# Control.net
KiCad netlist of a schematic drawn in Altium Designer
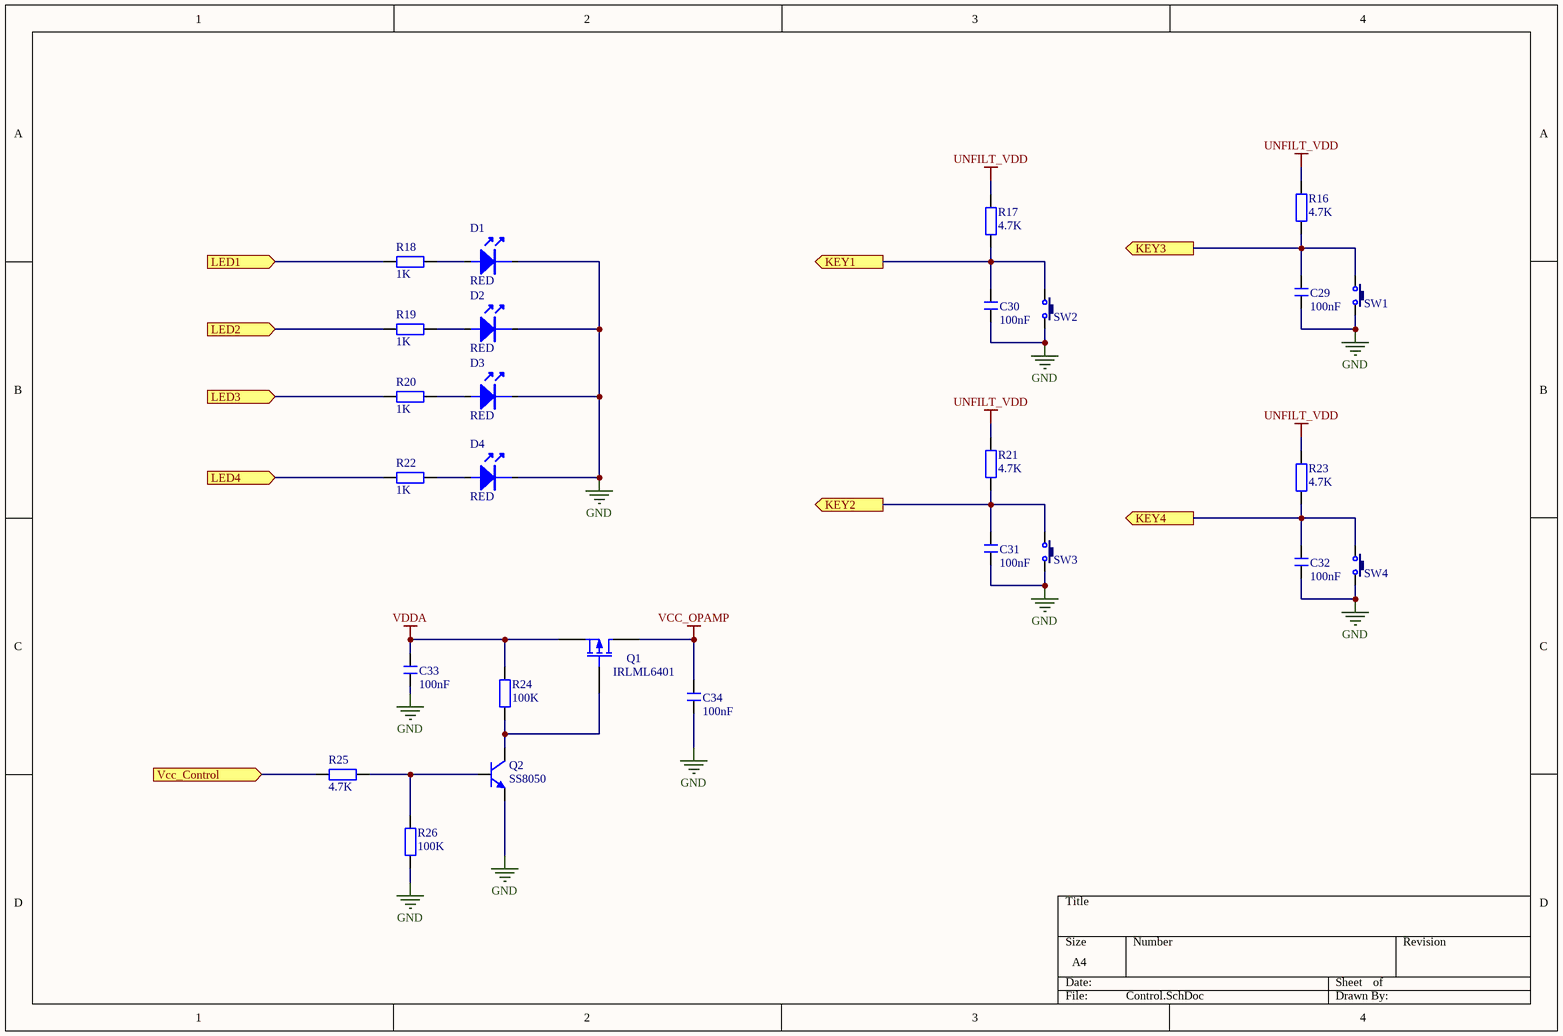
[diagram p0: Control.SchDoc]

(export (version "E")
  (design (tool "Eeschema 10.0.6"))
  (components
    (comp (ref "C29")
      (value "100nF")
      (footprint "C 0603_L")
      (description "贴片电容")
      (libsource (lib "0.1 - 电阻-电容-电感") (part "C"))
    )
    (comp (ref "C30")
      (value "100nF")
      (footprint "C 0603_L")
      (description "贴片电容")
      (libsource (lib "0.1 - 电阻-电容-电感") (part "C"))
    )
    (comp (ref "C31")
      (value "100nF")
      (footprint "C 0603_L")
      (description "贴片电容")
      (libsource (lib "0.1 - 电阻-电容-电感") (part "C"))
    )
    (comp (ref "C32")
      (value "100nF")
      (footprint "C 0603_L")
      (description "贴片电容")
      (libsource (lib "0.1 - 电阻-电容-电感") (part "C"))
    )
    (comp (ref "C33")
      (value "100nF")
      (footprint "C 0603_L")
      (description "贴片电容")
      (libsource (lib "0.1 - 电阻-电容-电感") (part "C"))
    )
    (comp (ref "C34")
      (value "100nF")
      (footprint "C 0603_L")
      (description "贴片电容")
      (libsource (lib "0.1 - 电阻-电容-电感") (part "C"))
    )
    (comp (ref "D1") (value "RED") (footprint "0603D") (libsource (lib "YS-F1Pro开发板主板") (part "LED")))
    (comp (ref "D2") (value "RED") (footprint "0603D") (libsource (lib "YS-F1Pro开发板主板") (part "LED")))
    (comp (ref "D3") (value "RED") (footprint "0603D") (libsource (lib "YS-F1Pro开发板主板") (part "LED")))
    (comp (ref "D4") (value "RED") (footprint "0603D") (libsource (lib "YS-F1Pro开发板主板") (part "LED")))
    (comp (ref "Q1")
      (value "IRLML6401")
      (footprint "mini_rlc:SOT-23_N")
      (description "P-Channel MOSFET")
      (fields (field (name "PUBLISHER") "Altium Limited"))
      (libsource (lib "Miscellaneous Devices") (part "MOSFET-P"))
    )
    (comp (ref "Q2")
      (value "SS8050")
      (footprint "SOT23-3N")
      (description "高频放大-NPN型")
      (fields (field (name "版权归属") "封装库来自淘宝 ID：黄晶宝石"))
      (libsource (lib "0.4 - 三极管") (part "8050-SMD"))
    )
    (comp (ref "R16")
      (value "4.7K")
      (footprint "R 0603_L")
      (description "贴片电阻")
      (fields (field (name "版权归属") "来自淘宝 ID：黄晶宝石"))
      (libsource (lib "0.1 - 电阻-电容-电感") (part "R"))
    )
    (comp (ref "R17")
      (value "4.7K")
      (footprint "R 0603_L")
      (description "贴片电阻")
      (fields (field (name "版权归属") "来自淘宝 ID：黄晶宝石"))
      (libsource (lib "0.1 - 电阻-电容-电感") (part "R"))
    )
    (comp (ref "R18")
      (value "1K")
      (footprint "R 0603_L")
      (description "贴片电阻")
      (fields (field (name "版权归属") "来自淘宝 ID：黄晶宝石"))
      (libsource (lib "0.1 - 电阻-电容-电感") (part "R"))
    )
    (comp (ref "R19")
      (value "1K")
      (footprint "R 0603_L")
      (description "贴片电阻")
      (fields (field (name "版权归属") "来自淘宝 ID：黄晶宝石"))
      (libsource (lib "0.1 - 电阻-电容-电感") (part "R"))
    )
    (comp (ref "R20")
      (value "1K")
      (footprint "R 0603_L")
      (description "贴片电阻")
      (fields (field (name "版权归属") "来自淘宝 ID：黄晶宝石"))
      (libsource (lib "0.1 - 电阻-电容-电感") (part "R"))
    )
    (comp (ref "R21")
      (value "4.7K")
      (footprint "R 0603_L")
      (description "贴片电阻")
      (fields (field (name "版权归属") "来自淘宝 ID：黄晶宝石"))
      (libsource (lib "0.1 - 电阻-电容-电感") (part "R"))
    )
    (comp (ref "R22")
      (value "1K")
      (footprint "R 0603_L")
      (description "贴片电阻")
      (fields (field (name "版权归属") "来自淘宝 ID：黄晶宝石"))
      (libsource (lib "0.1 - 电阻-电容-电感") (part "R"))
    )
    (comp (ref "R23")
      (value "4.7K")
      (footprint "R 0603_L")
      (description "贴片电阻")
      (fields (field (name "版权归属") "来自淘宝 ID：黄晶宝石"))
      (libsource (lib "0.1 - 电阻-电容-电感") (part "R"))
    )
    (comp (ref "R24")
      (value "100K")
      (footprint "R 0603_L")
      (description "贴片电阻")
      (fields (field (name "版权归属") "来自淘宝 ID：黄晶宝石"))
      (libsource (lib "0.1 - 电阻-电容-电感") (part "R"))
    )
    (comp (ref "R25")
      (value "4.7K")
      (footprint "R 0603_L")
      (description "贴片电阻")
      (fields (field (name "版权归属") "来自淘宝 ID：黄晶宝石"))
      (libsource (lib "0.1 - 电阻-电容-电感") (part "R"))
    )
    (comp (ref "R26")
      (value "100K")
      (footprint "R 0603_L")
      (description "贴片电阻")
      (fields (field (name "版权归属") "来自淘宝 ID：黄晶宝石"))
      (libsource (lib "0.1 - 电阻-电容-电感") (part "R"))
    )
    (comp (ref "SW1")
      (value "3x6x5")
      (footprint "TSW SMD-3*6*2.5")
      (description "3x6轻触开关")
      (fields (field (name "版权归属") "封装库来自淘宝 ID：黄晶宝石"))
      (libsource (lib "0.7 - 常用按键-开关") (part "TSW 3x6"))
    )
    (comp (ref "SW2")
      (value "3x6x5")
      (footprint "TSW SMD-3*6*2.5")
      (description "3x6轻触开关")
      (fields (field (name "版权归属") "封装库来自淘宝 ID：黄晶宝石"))
      (libsource (lib "0.7 - 常用按键-开关") (part "TSW 3x6"))
    )
    (comp (ref "SW3")
      (value "3x6x5")
      (footprint "TSW SMD-3*6*2.5")
      (description "3x6轻触开关")
      (fields (field (name "版权归属") "封装库来自淘宝 ID：黄晶宝石"))
      (libsource (lib "0.7 - 常用按键-开关") (part "TSW 3x6"))
    )
    (comp (ref "SW4")
      (value "3x6x5")
      (footprint "TSW SMD-3*6*2.5")
      (description "3x6轻触开关")
      (fields (field (name "版权归属") "封装库来自淘宝 ID：黄晶宝石"))
      (libsource (lib "0.7 - 常用按键-开关") (part "TSW 3x6"))
    )
  )
  (nets
    (net (code "1") (name "/KEY1") (class "Default")
      (node (ref "C30") (pin "1") (pinfunction "1_1") (pintype "passive"))
      (node (ref "R17") (pin "1") (pinfunction "1_1") (pintype "passive"))
      (node (ref "SW2") (pin "1") (pinfunction "1_1") (pintype "passive"))
    )
    (net (code "2") (name "/KEY2") (class "Default")
      (node (ref "C31") (pin "1") (pinfunction "1_1") (pintype "passive"))
      (node (ref "R21") (pin "1") (pinfunction "1_1") (pintype "passive"))
      (node (ref "SW3") (pin "1") (pinfunction "1_1") (pintype "passive"))
    )
    (net (code "3") (name "/KEY3") (class "Default")
      (node (ref "C29") (pin "1") (pinfunction "1_1") (pintype "passive"))
      (node (ref "R16") (pin "1") (pinfunction "1_1") (pintype "passive"))
      (node (ref "SW1") (pin "1") (pinfunction "1_1") (pintype "passive"))
    )
    (net (code "4") (name "/KEY4") (class "Default")
      (node (ref "C32") (pin "1") (pinfunction "1_1") (pintype "passive"))
      (node (ref "R23") (pin "1") (pinfunction "1_1") (pintype "passive"))
      (node (ref "SW4") (pin "1") (pinfunction "1_1") (pintype "passive"))
    )
    (net (code "5") (name "/LED1") (class "Default")
      (node (ref "R18") (pin "1") (pinfunction "1_1") (pintype "passive"))
    )
    (net (code "6") (name "/LED2") (class "Default")
      (node (ref "R19") (pin "1") (pinfunction "1_1") (pintype "passive"))
    )
    (net (code "7") (name "/LED3") (class "Default")
      (node (ref "R20") (pin "1") (pinfunction "1_1") (pintype "passive"))
    )
    (net (code "8") (name "/LED4") (class "Default")
      (node (ref "R22") (pin "1") (pinfunction "1_1") (pintype "passive"))
    )
    (net (code "9") (name "/Vcc_Control") (class "Default")
      (node (ref "R25") (pin "2") (pinfunction "2_2") (pintype "passive"))
    )
    (net (code "10") (name "GND") (class "Default")
      (node (ref "C29") (pin "2") (pinfunction "2_2") (pintype "passive"))
      (node (ref "C30") (pin "2") (pinfunction "2_2") (pintype "passive"))
      (node (ref "C31") (pin "2") (pinfunction "2_2") (pintype "passive"))
      (node (ref "C32") (pin "2") (pinfunction "2_2") (pintype "passive"))
      (node (ref "C33") (pin "1") (pinfunction "1_1") (pintype "passive"))
      (node (ref "C34") (pin "1") (pinfunction "1_1") (pintype "passive"))
      (node (ref "D1") (pin "2") (pinfunction "2_2") (pintype "passive"))
      (node (ref "D2") (pin "2") (pinfunction "2_2") (pintype "passive"))
      (node (ref "D3") (pin "2") (pinfunction "2_2") (pintype "passive"))
      (node (ref "D4") (pin "2") (pinfunction "2_2") (pintype "passive"))
      (node (ref "Q2") (pin "2") (pinfunction "E_2") (pintype "passive"))
      (node (ref "R26") (pin "2") (pinfunction "2_2") (pintype "passive"))
      (node (ref "SW1") (pin "2") (pinfunction "2_2") (pintype "passive"))
      (node (ref "SW2") (pin "2") (pinfunction "2_2") (pintype "passive"))
      (node (ref "SW3") (pin "2") (pinfunction "2_2") (pintype "passive"))
      (node (ref "SW4") (pin "2") (pinfunction "2_2") (pintype "passive"))
    )
    (net (code "11") (name "Net-(D1-Pad1)") (class "Default")
      (node (ref "D1") (pin "1") (pinfunction "1_1") (pintype "passive"))
      (node (ref "R18") (pin "2") (pinfunction "2_2") (pintype "passive"))
    )
    (net (code "12") (name "Net-(D2-Pad1)") (class "Default")
      (node (ref "D2") (pin "1") (pinfunction "1_1") (pintype "passive"))
      (node (ref "R19") (pin "2") (pinfunction "2_2") (pintype "passive"))
    )
    (net (code "13") (name "Net-(D3-Pad1)") (class "Default")
      (node (ref "D3") (pin "1") (pinfunction "1_1") (pintype "passive"))
      (node (ref "R20") (pin "2") (pinfunction "2_2") (pintype "passive"))
    )
    (net (code "14") (name "Net-(D4-Pad1)") (class "Default")
      (node (ref "D4") (pin "1") (pinfunction "1_1") (pintype "passive"))
      (node (ref "R22") (pin "2") (pinfunction "2_2") (pintype "passive"))
    )
    (net (code "15") (name "Net-(Q1-G)") (class "Default")
      (node (ref "Q1") (pin "1") (pinfunction "G_1") (pintype "passive"))
      (node (ref "Q2") (pin "3") (pinfunction "C_3") (pintype "passive"))
      (node (ref "R24") (pin "2") (pinfunction "2_2") (pintype "passive"))
    )
    (net (code "16") (name "Net-(Q2-B)") (class "Default")
      (node (ref "Q2") (pin "1") (pinfunction "B_1") (pintype "passive"))
      (node (ref "R25") (pin "1") (pinfunction "1_1") (pintype "passive"))
      (node (ref "R26") (pin "1") (pinfunction "1_1") (pintype "passive"))
    )
    (net (code "17") (name "UNFILT_VDD") (class "Default")
      (node (ref "R16") (pin "2") (pinfunction "2_2") (pintype "passive"))
      (node (ref "R17") (pin "2") (pinfunction "2_2") (pintype "passive"))
      (node (ref "R21") (pin "2") (pinfunction "2_2") (pintype "passive"))
      (node (ref "R23") (pin "2") (pinfunction "2_2") (pintype "passive"))
    )
    (net (code "18") (name "VCC_OPAMP") (class "Default")
      (node (ref "C34") (pin "2") (pinfunction "2_2") (pintype "passive"))
      (node (ref "Q1") (pin "3") (pinfunction "D_3") (pintype "passive"))
    )
    (net (code "19") (name "VDDA") (class "Default")
      (node (ref "C33") (pin "2") (pinfunction "2_2") (pintype "passive"))
      (node (ref "Q1") (pin "2") (pinfunction "S_2") (pintype "passive"))
      (node (ref "R24") (pin "1") (pinfunction "1_1") (pintype "passive"))
    )
  )
)
